# main.net
KiCad netlist of a schematic drawn in EAGLE
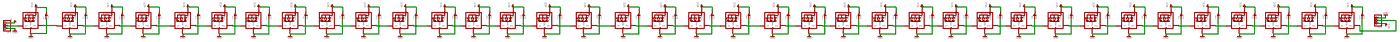
[diagram p0: schematic, sheet 1, overview]
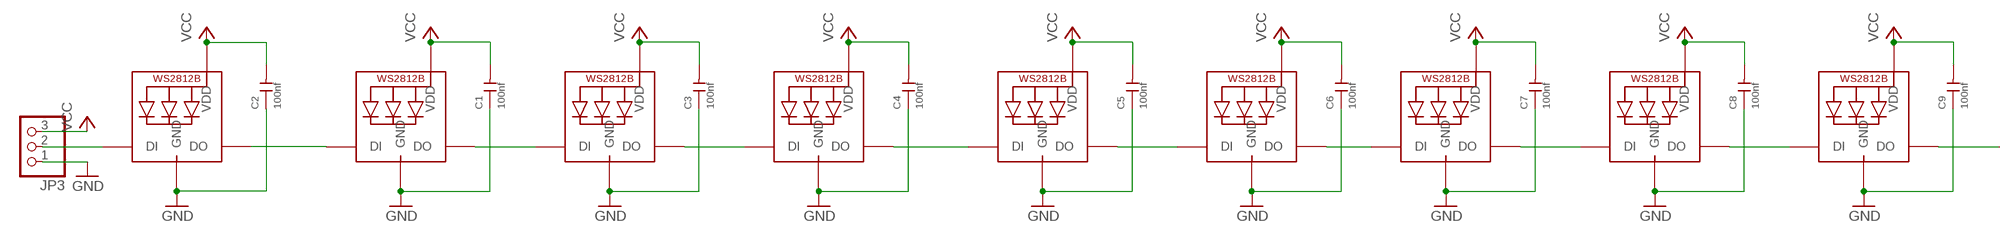
[diagram p1: schematic, sheet 1, part 1 of 4]
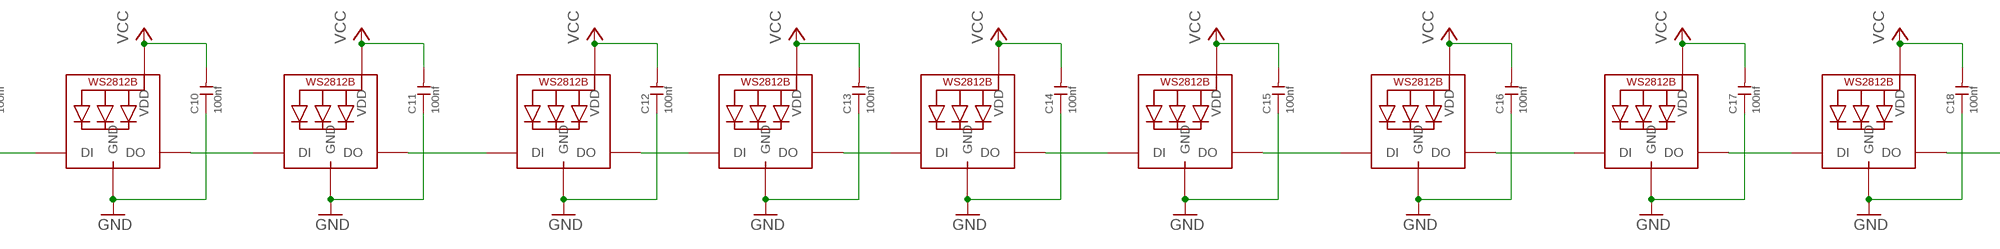
[diagram p2: schematic, sheet 1, part 2 of 4]
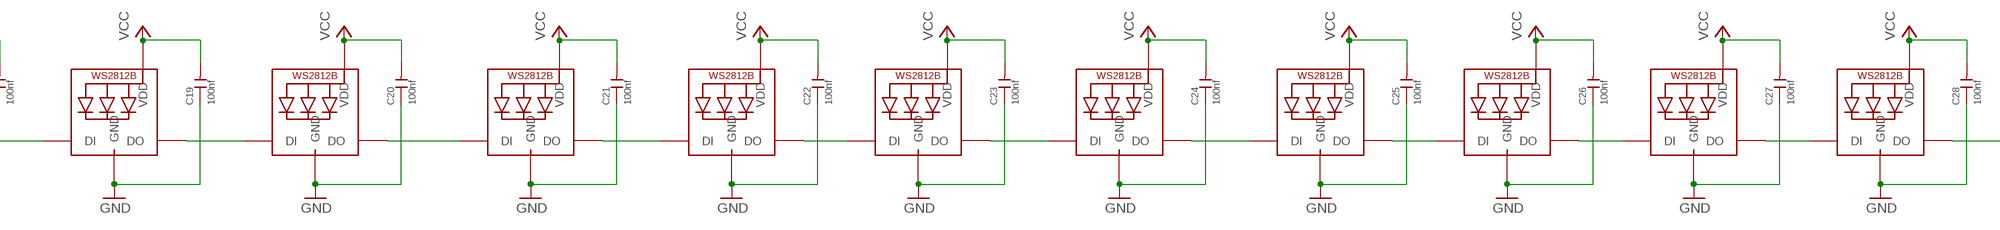
[diagram p3: schematic, sheet 1, part 3 of 4]
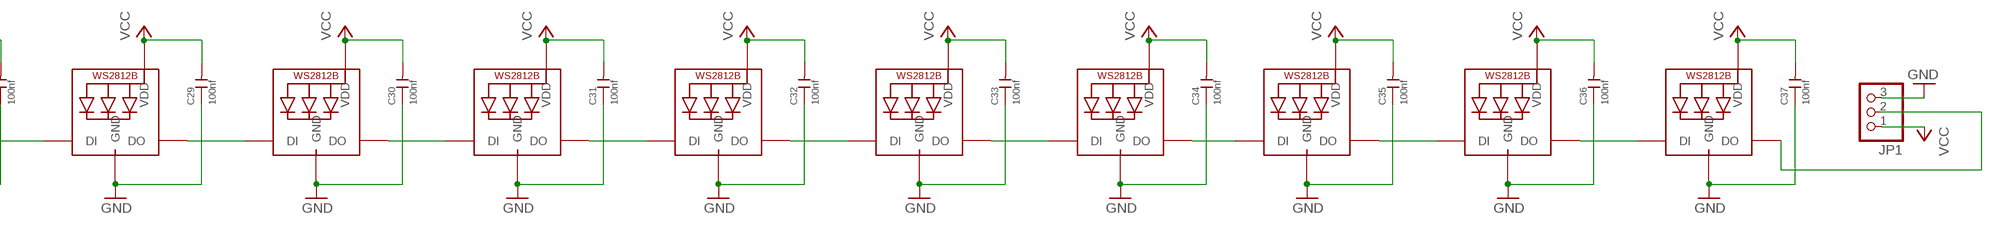
[diagram p4: schematic, sheet 1, part 4 of 4]

(export (version "E")
  (design (tool "Eeschema 10.0.6"))
  (components
    (comp (ref "C1")
      (value "100nf")
      (footprint "eagle-import:C0402")
      (fields (field (name "MPN") "CC0402KRX7R8BB104"))
      (libsource (lib "eagle-import") (part "CERAMIC-100NF-25V-10%-X7R(0402)"))
    )
    (comp (ref "C2")
      (value "100nf")
      (footprint "eagle-import:C0402")
      (fields (field (name "MPN") "CC0402KRX7R8BB104"))
      (libsource (lib "eagle-import") (part "CERAMIC-100NF-25V-10%-X7R(0402)"))
    )
    (comp (ref "C3")
      (value "100nf")
      (footprint "eagle-import:C0402")
      (fields (field (name "MPN") "CC0402KRX7R8BB104"))
      (libsource (lib "eagle-import") (part "CERAMIC-100NF-25V-10%-X7R(0402)"))
    )
    (comp (ref "C4")
      (value "100nf")
      (footprint "eagle-import:C0402")
      (fields (field (name "MPN") "CC0402KRX7R8BB104"))
      (libsource (lib "eagle-import") (part "CERAMIC-100NF-25V-10%-X7R(0402)"))
    )
    (comp (ref "C5")
      (value "100nf")
      (footprint "eagle-import:C0402")
      (fields (field (name "MPN") "CC0402KRX7R8BB104"))
      (libsource (lib "eagle-import") (part "CERAMIC-100NF-25V-10%-X7R(0402)"))
    )
    (comp (ref "C6")
      (value "100nf")
      (footprint "eagle-import:C0402")
      (fields (field (name "MPN") "CC0402KRX7R8BB104"))
      (libsource (lib "eagle-import") (part "CERAMIC-100NF-25V-10%-X7R(0402)"))
    )
    (comp (ref "C7")
      (value "100nf")
      (footprint "eagle-import:C0402")
      (fields (field (name "MPN") "CC0402KRX7R8BB104"))
      (libsource (lib "eagle-import") (part "CERAMIC-100NF-25V-10%-X7R(0402)"))
    )
    (comp (ref "C8")
      (value "100nf")
      (footprint "eagle-import:C0402")
      (fields (field (name "MPN") "CC0402KRX7R8BB104"))
      (libsource (lib "eagle-import") (part "CERAMIC-100NF-25V-10%-X7R(0402)"))
    )
    (comp (ref "C9")
      (value "100nf")
      (footprint "eagle-import:C0402")
      (fields (field (name "MPN") "CC0402KRX7R8BB104"))
      (libsource (lib "eagle-import") (part "CERAMIC-100NF-25V-10%-X7R(0402)"))
    )
    (comp (ref "C10")
      (value "100nf")
      (footprint "eagle-import:C0402")
      (fields (field (name "MPN") "CC0402KRX7R8BB104"))
      (libsource (lib "eagle-import") (part "CERAMIC-100NF-25V-10%-X7R(0402)"))
    )
    (comp (ref "C11")
      (value "100nf")
      (footprint "eagle-import:C0402")
      (fields (field (name "MPN") "CC0402KRX7R8BB104"))
      (libsource (lib "eagle-import") (part "CERAMIC-100NF-25V-10%-X7R(0402)"))
    )
    (comp (ref "C12")
      (value "100nf")
      (footprint "eagle-import:C0402")
      (fields (field (name "MPN") "CC0402KRX7R8BB104"))
      (libsource (lib "eagle-import") (part "CERAMIC-100NF-25V-10%-X7R(0402)"))
    )
    (comp (ref "C13")
      (value "100nf")
      (footprint "eagle-import:C0402")
      (fields (field (name "MPN") "CC0402KRX7R8BB104"))
      (libsource (lib "eagle-import") (part "CERAMIC-100NF-25V-10%-X7R(0402)"))
    )
    (comp (ref "C14")
      (value "100nf")
      (footprint "eagle-import:C0402")
      (fields (field (name "MPN") "CC0402KRX7R8BB104"))
      (libsource (lib "eagle-import") (part "CERAMIC-100NF-25V-10%-X7R(0402)"))
    )
    (comp (ref "C15")
      (value "100nf")
      (footprint "eagle-import:C0402")
      (fields (field (name "MPN") "CC0402KRX7R8BB104"))
      (libsource (lib "eagle-import") (part "CERAMIC-100NF-25V-10%-X7R(0402)"))
    )
    (comp (ref "C16")
      (value "100nf")
      (footprint "eagle-import:C0402")
      (fields (field (name "MPN") "CC0402KRX7R8BB104"))
      (libsource (lib "eagle-import") (part "CERAMIC-100NF-25V-10%-X7R(0402)"))
    )
    (comp (ref "C17")
      (value "100nf")
      (footprint "eagle-import:C0402")
      (fields (field (name "MPN") "CC0402KRX7R8BB104"))
      (libsource (lib "eagle-import") (part "CERAMIC-100NF-25V-10%-X7R(0402)"))
    )
    (comp (ref "C18")
      (value "100nf")
      (footprint "eagle-import:C0402")
      (fields (field (name "MPN") "CC0402KRX7R8BB104"))
      (libsource (lib "eagle-import") (part "CERAMIC-100NF-25V-10%-X7R(0402)"))
    )
    (comp (ref "C19")
      (value "100nf")
      (footprint "eagle-import:C0402")
      (fields (field (name "MPN") "CC0402KRX7R8BB104"))
      (libsource (lib "eagle-import") (part "CERAMIC-100NF-25V-10%-X7R(0402)"))
    )
    (comp (ref "C20")
      (value "100nf")
      (footprint "eagle-import:C0402")
      (fields (field (name "MPN") "CC0402KRX7R8BB104"))
      (libsource (lib "eagle-import") (part "CERAMIC-100NF-25V-10%-X7R(0402)"))
    )
    (comp (ref "C21")
      (value "100nf")
      (footprint "eagle-import:C0402")
      (fields (field (name "MPN") "CC0402KRX7R8BB104"))
      (libsource (lib "eagle-import") (part "CERAMIC-100NF-25V-10%-X7R(0402)"))
    )
    (comp (ref "C22")
      (value "100nf")
      (footprint "eagle-import:C0402")
      (fields (field (name "MPN") "CC0402KRX7R8BB104"))
      (libsource (lib "eagle-import") (part "CERAMIC-100NF-25V-10%-X7R(0402)"))
    )
    (comp (ref "C23")
      (value "100nf")
      (footprint "eagle-import:C0402")
      (fields (field (name "MPN") "CC0402KRX7R8BB104"))
      (libsource (lib "eagle-import") (part "CERAMIC-100NF-25V-10%-X7R(0402)"))
    )
    (comp (ref "C24")
      (value "100nf")
      (footprint "eagle-import:C0402")
      (fields (field (name "MPN") "CC0402KRX7R8BB104"))
      (libsource (lib "eagle-import") (part "CERAMIC-100NF-25V-10%-X7R(0402)"))
    )
    (comp (ref "C25")
      (value "100nf")
      (footprint "eagle-import:C0402")
      (fields (field (name "MPN") "CC0402KRX7R8BB104"))
      (libsource (lib "eagle-import") (part "CERAMIC-100NF-25V-10%-X7R(0402)"))
    )
    (comp (ref "C26")
      (value "100nf")
      (footprint "eagle-import:C0402")
      (fields (field (name "MPN") "CC0402KRX7R8BB104"))
      (libsource (lib "eagle-import") (part "CERAMIC-100NF-25V-10%-X7R(0402)"))
    )
    (comp (ref "C27")
      (value "100nf")
      (footprint "eagle-import:C0402")
      (fields (field (name "MPN") "CC0402KRX7R8BB104"))
      (libsource (lib "eagle-import") (part "CERAMIC-100NF-25V-10%-X7R(0402)"))
    )
    (comp (ref "C28")
      (value "100nf")
      (footprint "eagle-import:C0402")
      (fields (field (name "MPN") "CC0402KRX7R8BB104"))
      (libsource (lib "eagle-import") (part "CERAMIC-100NF-25V-10%-X7R(0402)"))
    )
    (comp (ref "C29")
      (value "100nf")
      (footprint "eagle-import:C0402")
      (fields (field (name "MPN") "CC0402KRX7R8BB104"))
      (libsource (lib "eagle-import") (part "CERAMIC-100NF-25V-10%-X7R(0402)"))
    )
    (comp (ref "C30")
      (value "100nf")
      (footprint "eagle-import:C0402")
      (fields (field (name "MPN") "CC0402KRX7R8BB104"))
      (libsource (lib "eagle-import") (part "CERAMIC-100NF-25V-10%-X7R(0402)"))
    )
    (comp (ref "C31")
      (value "100nf")
      (footprint "eagle-import:C0402")
      (fields (field (name "MPN") "CC0402KRX7R8BB104"))
      (libsource (lib "eagle-import") (part "CERAMIC-100NF-25V-10%-X7R(0402)"))
    )
    (comp (ref "C32")
      (value "100nf")
      (footprint "eagle-import:C0402")
      (fields (field (name "MPN") "CC0402KRX7R8BB104"))
      (libsource (lib "eagle-import") (part "CERAMIC-100NF-25V-10%-X7R(0402)"))
    )
    (comp (ref "C33")
      (value "100nf")
      (footprint "eagle-import:C0402")
      (fields (field (name "MPN") "CC0402KRX7R8BB104"))
      (libsource (lib "eagle-import") (part "CERAMIC-100NF-25V-10%-X7R(0402)"))
    )
    (comp (ref "C34")
      (value "100nf")
      (footprint "eagle-import:C0402")
      (fields (field (name "MPN") "CC0402KRX7R8BB104"))
      (libsource (lib "eagle-import") (part "CERAMIC-100NF-25V-10%-X7R(0402)"))
    )
    (comp (ref "C35")
      (value "100nf")
      (footprint "eagle-import:C0402")
      (fields (field (name "MPN") "CC0402KRX7R8BB104"))
      (libsource (lib "eagle-import") (part "CERAMIC-100NF-25V-10%-X7R(0402)"))
    )
    (comp (ref "C36")
      (value "100nf")
      (footprint "eagle-import:C0402")
      (fields (field (name "MPN") "CC0402KRX7R8BB104"))
      (libsource (lib "eagle-import") (part "CERAMIC-100NF-25V-10%-X7R(0402)"))
    )
    (comp (ref "C37")
      (value "100nf")
      (footprint "eagle-import:C0402")
      (fields (field (name "MPN") "CC0402KRX7R8BB104"))
      (libsource (lib "eagle-import") (part "CERAMIC-100NF-25V-10%-X7R(0402)"))
    )
    (comp (ref "JP1")
      (value "PINHD-1X3")
      (footprint "eagle-import:1X03")
      (libsource (lib "eagle-import") (part "PINHD-1X3"))
    )
    (comp (ref "JP3")
      (value "PINHD-1X3")
      (footprint "eagle-import:1X03")
      (libsource (lib "eagle-import") (part "PINHD-1X3"))
    )
    (comp (ref "L")
      (value "WS2812B5050")
      (footprint "eagle-import:WS2812B")
      (libsource (lib "eagle-import") (part "WS2812B5050"))
    )
    (comp (ref "LED1")
      (value "WS2812B5050")
      (footprint "eagle-import:WS2812B")
      (libsource (lib "eagle-import") (part "WS2812B5050"))
    )
    (comp (ref "LED3")
      (value "WS2812B5050")
      (footprint "eagle-import:WS2812B")
      (libsource (lib "eagle-import") (part "WS2812B5050"))
    )
    (comp (ref "LED4")
      (value "WS2812B5050")
      (footprint "eagle-import:WS2812B")
      (libsource (lib "eagle-import") (part "WS2812B5050"))
    )
    (comp (ref "LED5")
      (value "WS2812B5050")
      (footprint "eagle-import:WS2812B")
      (libsource (lib "eagle-import") (part "WS2812B5050"))
    )
    (comp (ref "LED6")
      (value "WS2812B5050")
      (footprint "eagle-import:WS2812B")
      (libsource (lib "eagle-import") (part "WS2812B5050"))
    )
    (comp (ref "LED7")
      (value "WS2812B5050")
      (footprint "eagle-import:WS2812B")
      (libsource (lib "eagle-import") (part "WS2812B5050"))
    )
    (comp (ref "LED8")
      (value "WS2812B5050")
      (footprint "eagle-import:WS2812B")
      (libsource (lib "eagle-import") (part "WS2812B5050"))
    )
    (comp (ref "LED9")
      (value "WS2812B5050")
      (footprint "eagle-import:WS2812B")
      (libsource (lib "eagle-import") (part "WS2812B5050"))
    )
    (comp (ref "LED10")
      (value "WS2812B5050")
      (footprint "eagle-import:WS2812B")
      (libsource (lib "eagle-import") (part "WS2812B5050"))
    )
    (comp (ref "LED11")
      (value "WS2812B5050")
      (footprint "eagle-import:WS2812B")
      (libsource (lib "eagle-import") (part "WS2812B5050"))
    )
    (comp (ref "LED12")
      (value "WS2812B5050")
      (footprint "eagle-import:WS2812B")
      (libsource (lib "eagle-import") (part "WS2812B5050"))
    )
    (comp (ref "LED13")
      (value "WS2812B5050")
      (footprint "eagle-import:WS2812B")
      (libsource (lib "eagle-import") (part "WS2812B5050"))
    )
    (comp (ref "LED14")
      (value "WS2812B5050")
      (footprint "eagle-import:WS2812B")
      (libsource (lib "eagle-import") (part "WS2812B5050"))
    )
    (comp (ref "LED15")
      (value "WS2812B5050")
      (footprint "eagle-import:WS2812B")
      (libsource (lib "eagle-import") (part "WS2812B5050"))
    )
    (comp (ref "LED16")
      (value "WS2812B5050")
      (footprint "eagle-import:WS2812B")
      (libsource (lib "eagle-import") (part "WS2812B5050"))
    )
    (comp (ref "LED17")
      (value "WS2812B5050")
      (footprint "eagle-import:WS2812B")
      (libsource (lib "eagle-import") (part "WS2812B5050"))
    )
    (comp (ref "LED18")
      (value "WS2812B5050")
      (footprint "eagle-import:WS2812B")
      (libsource (lib "eagle-import") (part "WS2812B5050"))
    )
    (comp (ref "LED19")
      (value "WS2812B5050")
      (footprint "eagle-import:WS2812B")
      (libsource (lib "eagle-import") (part "WS2812B5050"))
    )
    (comp (ref "LED20")
      (value "WS2812B5050")
      (footprint "eagle-import:WS2812B")
      (libsource (lib "eagle-import") (part "WS2812B5050"))
    )
    (comp (ref "LED21")
      (value "WS2812B5050")
      (footprint "eagle-import:WS2812B")
      (libsource (lib "eagle-import") (part "WS2812B5050"))
    )
    (comp (ref "LED22")
      (value "WS2812B5050")
      (footprint "eagle-import:WS2812B")
      (libsource (lib "eagle-import") (part "WS2812B5050"))
    )
    (comp (ref "LED23")
      (value "WS2812B5050")
      (footprint "eagle-import:WS2812B")
      (libsource (lib "eagle-import") (part "WS2812B5050"))
    )
    (comp (ref "LED24")
      (value "WS2812B5050")
      (footprint "eagle-import:WS2812B")
      (libsource (lib "eagle-import") (part "WS2812B5050"))
    )
    (comp (ref "LED25")
      (value "WS2812B5050")
      (footprint "eagle-import:WS2812B")
      (libsource (lib "eagle-import") (part "WS2812B5050"))
    )
    (comp (ref "LED26")
      (value "WS2812B5050")
      (footprint "eagle-import:WS2812B")
      (libsource (lib "eagle-import") (part "WS2812B5050"))
    )
    (comp (ref "LED27")
      (value "WS2812B5050")
      (footprint "eagle-import:WS2812B")
      (libsource (lib "eagle-import") (part "WS2812B5050"))
    )
    (comp (ref "LED28")
      (value "WS2812B5050")
      (footprint "eagle-import:WS2812B")
      (libsource (lib "eagle-import") (part "WS2812B5050"))
    )
    (comp (ref "LED29")
      (value "WS2812B5050")
      (footprint "eagle-import:WS2812B")
      (libsource (lib "eagle-import") (part "WS2812B5050"))
    )
    (comp (ref "LED30")
      (value "WS2812B5050")
      (footprint "eagle-import:WS2812B")
      (libsource (lib "eagle-import") (part "WS2812B5050"))
    )
    (comp (ref "LED31")
      (value "WS2812B5050")
      (footprint "eagle-import:WS2812B")
      (libsource (lib "eagle-import") (part "WS2812B5050"))
    )
    (comp (ref "LED32")
      (value "WS2812B5050")
      (footprint "eagle-import:WS2812B")
      (libsource (lib "eagle-import") (part "WS2812B5050"))
    )
    (comp (ref "LED33")
      (value "WS2812B5050")
      (footprint "eagle-import:WS2812B")
      (libsource (lib "eagle-import") (part "WS2812B5050"))
    )
    (comp (ref "LED34")
      (value "WS2812B5050")
      (footprint "eagle-import:WS2812B")
      (libsource (lib "eagle-import") (part "WS2812B5050"))
    )
    (comp (ref "LED35")
      (value "WS2812B5050")
      (footprint "eagle-import:WS2812B")
      (libsource (lib "eagle-import") (part "WS2812B5050"))
    )
    (comp (ref "LED36")
      (value "WS2812B5050")
      (footprint "eagle-import:WS2812B")
      (libsource (lib "eagle-import") (part "WS2812B5050"))
    )
    (comp (ref "LED37")
      (value "WS2812B5050")
      (footprint "eagle-import:WS2812B")
      (libsource (lib "eagle-import") (part "WS2812B5050"))
    )
  )
  (nets
    (net (code "1") (name "GND") (class "Default")
      (node (ref "C1") (pin "1") (pinfunction "1_1") (pintype "passive"))
      (node (ref "C10") (pin "1") (pinfunction "1_1") (pintype "passive"))
      (node (ref "C11") (pin "1") (pinfunction "1_1") (pintype "passive"))
      (node (ref "C12") (pin "1") (pinfunction "1_1") (pintype "passive"))
      (node (ref "C13") (pin "1") (pinfunction "1_1") (pintype "passive"))
      (node (ref "C14") (pin "1") (pinfunction "1_1") (pintype "passive"))
      (node (ref "C15") (pin "1") (pinfunction "1_1") (pintype "passive"))
      (node (ref "C16") (pin "1") (pinfunction "1_1") (pintype "passive"))
      (node (ref "C17") (pin "1") (pinfunction "1_1") (pintype "passive"))
      (node (ref "C18") (pin "1") (pinfunction "1_1") (pintype "passive"))
      (node (ref "C19") (pin "1") (pinfunction "1_1") (pintype "passive"))
      (node (ref "C2") (pin "1") (pinfunction "1_1") (pintype "passive"))
      (node (ref "C20") (pin "1") (pinfunction "1_1") (pintype "passive"))
      (node (ref "C21") (pin "1") (pinfunction "1_1") (pintype "passive"))
      (node (ref "C22") (pin "1") (pinfunction "1_1") (pintype "passive"))
      (node (ref "C23") (pin "1") (pinfunction "1_1") (pintype "passive"))
      (node (ref "C24") (pin "1") (pinfunction "1_1") (pintype "passive"))
      (node (ref "C25") (pin "1") (pinfunction "1_1") (pintype "passive"))
      (node (ref "C26") (pin "1") (pinfunction "1_1") (pintype "passive"))
      (node (ref "C27") (pin "1") (pinfunction "1_1") (pintype "passive"))
      (node (ref "C28") (pin "1") (pinfunction "1_1") (pintype "passive"))
      (node (ref "C29") (pin "1") (pinfunction "1_1") (pintype "passive"))
      (node (ref "C3") (pin "1") (pinfunction "1_1") (pintype "passive"))
      (node (ref "C30") (pin "1") (pinfunction "1_1") (pintype "passive"))
      (node (ref "C31") (pin "1") (pinfunction "1_1") (pintype "passive"))
      (node (ref "C32") (pin "1") (pinfunction "1_1") (pintype "passive"))
      (node (ref "C33") (pin "1") (pinfunction "1_1") (pintype "passive"))
      (node (ref "C34") (pin "1") (pinfunction "1_1") (pintype "passive"))
      (node (ref "C35") (pin "1") (pinfunction "1_1") (pintype "passive"))
      (node (ref "C36") (pin "1") (pinfunction "1_1") (pintype "passive"))
      (node (ref "C37") (pin "1") (pinfunction "1_1") (pintype "passive"))
      (node (ref "C4") (pin "1") (pinfunction "1_1") (pintype "passive"))
      (node (ref "C5") (pin "1") (pinfunction "1_1") (pintype "passive"))
      (node (ref "C6") (pin "1") (pinfunction "1_1") (pintype "passive"))
      (node (ref "C7") (pin "1") (pinfunction "1_1") (pintype "passive"))
      (node (ref "C8") (pin "1") (pinfunction "1_1") (pintype "passive"))
      (node (ref "C9") (pin "1") (pinfunction "1_1") (pintype "passive"))
      (node (ref "JP1") (pin "3") (pinfunction "3_3") (pintype "passive"))
      (node (ref "JP3") (pin "1") (pinfunction "1_1") (pintype "passive"))
      (node (ref "L") (pin "3-GND") (pinfunction "GND_3-GND") (pintype "power_in"))
      (node (ref "LED1") (pin "3-GND") (pinfunction "GND_3-GND") (pintype "power_in"))
      (node (ref "LED10") (pin "3-GND") (pinfunction "GND_3-GND") (pintype "power_in"))
      (node (ref "LED11") (pin "3-GND") (pinfunction "GND_3-GND") (pintype "power_in"))
      (node (ref "LED12") (pin "3-GND") (pinfunction "GND_3-GND") (pintype "power_in"))
      (node (ref "LED13") (pin "3-GND") (pinfunction "GND_3-GND") (pintype "power_in"))
      (node (ref "LED14") (pin "3-GND") (pinfunction "GND_3-GND") (pintype "power_in"))
      (node (ref "LED15") (pin "3-GND") (pinfunction "GND_3-GND") (pintype "power_in"))
      (node (ref "LED16") (pin "3-GND") (pinfunction "GND_3-GND") (pintype "power_in"))
      (node (ref "LED17") (pin "3-GND") (pinfunction "GND_3-GND") (pintype "power_in"))
      (node (ref "LED18") (pin "3-GND") (pinfunction "GND_3-GND") (pintype "power_in"))
      (node (ref "LED19") (pin "3-GND") (pinfunction "GND_3-GND") (pintype "power_in"))
      (node (ref "LED20") (pin "3-GND") (pinfunction "GND_3-GND") (pintype "power_in"))
      (node (ref "LED21") (pin "3-GND") (pinfunction "GND_3-GND") (pintype "power_in"))
      (node (ref "LED22") (pin "3-GND") (pinfunction "GND_3-GND") (pintype "power_in"))
      (node (ref "LED23") (pin "3-GND") (pinfunction "GND_3-GND") (pintype "power_in"))
      (node (ref "LED24") (pin "3-GND") (pinfunction "GND_3-GND") (pintype "power_in"))
      (node (ref "LED25") (pin "3-GND") (pinfunction "GND_3-GND") (pintype "power_in"))
      (node (ref "LED26") (pin "3-GND") (pinfunction "GND_3-GND") (pintype "power_in"))
      (node (ref "LED27") (pin "3-GND") (pinfunction "GND_3-GND") (pintype "power_in"))
      (node (ref "LED28") (pin "3-GND") (pinfunction "GND_3-GND") (pintype "power_in"))
      (node (ref "LED29") (pin "3-GND") (pinfunction "GND_3-GND") (pintype "power_in"))
      (node (ref "LED3") (pin "3-GND") (pinfunction "GND_3-GND") (pintype "power_in"))
      (node (ref "LED30") (pin "3-GND") (pinfunction "GND_3-GND") (pintype "power_in"))
      (node (ref "LED31") (pin "3-GND") (pinfunction "GND_3-GND") (pintype "power_in"))
      (node (ref "LED32") (pin "3-GND") (pinfunction "GND_3-GND") (pintype "power_in"))
      (node (ref "LED33") (pin "3-GND") (pinfunction "GND_3-GND") (pintype "power_in"))
      (node (ref "LED34") (pin "3-GND") (pinfunction "GND_3-GND") (pintype "power_in"))
      (node (ref "LED35") (pin "3-GND") (pinfunction "GND_3-GND") (pintype "power_in"))
      (node (ref "LED36") (pin "3-GND") (pinfunction "GND_3-GND") (pintype "power_in"))
      (node (ref "LED37") (pin "3-GND") (pinfunction "GND_3-GND") (pintype "power_in"))
      (node (ref "LED4") (pin "3-GND") (pinfunction "GND_3-GND") (pintype "power_in"))
      (node (ref "LED5") (pin "3-GND") (pinfunction "GND_3-GND") (pintype "power_in"))
      (node (ref "LED6") (pin "3-GND") (pinfunction "GND_3-GND") (pintype "power_in"))
      (node (ref "LED7") (pin "3-GND") (pinfunction "GND_3-GND") (pintype "power_in"))
      (node (ref "LED8") (pin "3-GND") (pinfunction "GND_3-GND") (pintype "power_in"))
      (node (ref "LED9") (pin "3-GND") (pinfunction "GND_3-GND") (pintype "power_in"))
    )
    (net (code "2") (name "Net-(L-DI)") (class "Default")
      (node (ref "JP3") (pin "2") (pinfunction "2_2") (pintype "passive"))
      (node (ref "L") (pin "4-DIN") (pinfunction "DI_4-DIN") (pintype "input"))
    )
    (net (code "3") (name "Net-(L-DO)") (class "Default")
      (node (ref "L") (pin "2-DOUT") (pinfunction "DO_2-DOUT") (pintype "output"))
      (node (ref "LED1") (pin "4-DIN") (pinfunction "DI_4-DIN") (pintype "input"))
    )
    (net (code "4") (name "Net-(LED1-DO)") (class "Default")
      (node (ref "LED1") (pin "2-DOUT") (pinfunction "DO_2-DOUT") (pintype "output"))
      (node (ref "LED3") (pin "4-DIN") (pinfunction "DI_4-DIN") (pintype "input"))
    )
    (net (code "5") (name "Net-(LED3-DO)") (class "Default")
      (node (ref "LED3") (pin "2-DOUT") (pinfunction "DO_2-DOUT") (pintype "output"))
      (node (ref "LED4") (pin "4-DIN") (pinfunction "DI_4-DIN") (pintype "input"))
    )
    (net (code "6") (name "Net-(LED4-DO)") (class "Default")
      (node (ref "LED4") (pin "2-DOUT") (pinfunction "DO_2-DOUT") (pintype "output"))
      (node (ref "LED5") (pin "4-DIN") (pinfunction "DI_4-DIN") (pintype "input"))
    )
    (net (code "7") (name "Net-(LED5-DO)") (class "Default")
      (node (ref "LED5") (pin "2-DOUT") (pinfunction "DO_2-DOUT") (pintype "output"))
      (node (ref "LED6") (pin "4-DIN") (pinfunction "DI_4-DIN") (pintype "input"))
    )
    (net (code "8") (name "Net-(LED6-DO)") (class "Default")
      (node (ref "LED6") (pin "2-DOUT") (pinfunction "DO_2-DOUT") (pintype "output"))
      (node (ref "LED7") (pin "4-DIN") (pinfunction "DI_4-DIN") (pintype "input"))
    )
    (net (code "9") (name "Net-(LED7-DO)") (class "Default")
      (node (ref "LED7") (pin "2-DOUT") (pinfunction "DO_2-DOUT") (pintype "output"))
      (node (ref "LED8") (pin "4-DIN") (pinfunction "DI_4-DIN") (pintype "input"))
    )
    (net (code "10") (name "Net-(LED8-DO)") (class "Default")
      (node (ref "LED8") (pin "2-DOUT") (pinfunction "DO_2-DOUT") (pintype "output"))
      (node (ref "LED9") (pin "4-DIN") (pinfunction "DI_4-DIN") (pintype "input"))
    )
    (net (code "11") (name "Net-(LED10-DI)") (class "Default")
      (node (ref "LED10") (pin "4-DIN") (pinfunction "DI_4-DIN") (pintype "input"))
      (node (ref "LED9") (pin "2-DOUT") (pinfunction "DO_2-DOUT") (pintype "output"))
    )
    (net (code "12") (name "Net-(LED10-DO)") (class "Default")
      (node (ref "LED10") (pin "2-DOUT") (pinfunction "DO_2-DOUT") (pintype "output"))
      (node (ref "LED11") (pin "4-DIN") (pinfunction "DI_4-DIN") (pintype "input"))
    )
    (net (code "13") (name "Net-(LED11-DO)") (class "Default")
      (node (ref "LED11") (pin "2-DOUT") (pinfunction "DO_2-DOUT") (pintype "output"))
      (node (ref "LED12") (pin "4-DIN") (pinfunction "DI_4-DIN") (pintype "input"))
    )
    (net (code "14") (name "Net-(LED12-DO)") (class "Default")
      (node (ref "LED12") (pin "2-DOUT") (pinfunction "DO_2-DOUT") (pintype "output"))
      (node (ref "LED13") (pin "4-DIN") (pinfunction "DI_4-DIN") (pintype "input"))
    )
    (net (code "15") (name "Net-(LED13-DO)") (class "Default")
      (node (ref "LED13") (pin "2-DOUT") (pinfunction "DO_2-DOUT") (pintype "output"))
      (node (ref "LED14") (pin "4-DIN") (pinfunction "DI_4-DIN") (pintype "input"))
    )
    (net (code "16") (name "Net-(LED14-DO)") (class "Default")
      (node (ref "LED14") (pin "2-DOUT") (pinfunction "DO_2-DOUT") (pintype "output"))
      (node (ref "LED15") (pin "4-DIN") (pinfunction "DI_4-DIN") (pintype "input"))
    )
    (net (code "17") (name "Net-(LED15-DO)") (class "Default")
      (node (ref "LED15") (pin "2-DOUT") (pinfunction "DO_2-DOUT") (pintype "output"))
      (node (ref "LED16") (pin "4-DIN") (pinfunction "DI_4-DIN") (pintype "input"))
    )
    (net (code "18") (name "Net-(LED16-DO)") (class "Default")
      (node (ref "LED16") (pin "2-DOUT") (pinfunction "DO_2-DOUT") (pintype "output"))
      (node (ref "LED17") (pin "4-DIN") (pinfunction "DI_4-DIN") (pintype "input"))
    )
    (net (code "19") (name "Net-(LED17-DO)") (class "Default")
      (node (ref "LED17") (pin "2-DOUT") (pinfunction "DO_2-DOUT") (pintype "output"))
      (node (ref "LED18") (pin "4-DIN") (pinfunction "DI_4-DIN") (pintype "input"))
    )
    (net (code "20") (name "Net-(LED18-DO)") (class "Default")
      (node (ref "LED18") (pin "2-DOUT") (pinfunction "DO_2-DOUT") (pintype "output"))
      (node (ref "LED19") (pin "4-DIN") (pinfunction "DI_4-DIN") (pintype "input"))
    )
    (net (code "21") (name "Net-(LED19-DO)") (class "Default")
      (node (ref "LED19") (pin "2-DOUT") (pinfunction "DO_2-DOUT") (pintype "output"))
      (node (ref "LED20") (pin "4-DIN") (pinfunction "DI_4-DIN") (pintype "input"))
    )
    (net (code "22") (name "Net-(LED20-DO)") (class "Default")
      (node (ref "LED20") (pin "2-DOUT") (pinfunction "DO_2-DOUT") (pintype "output"))
      (node (ref "LED21") (pin "4-DIN") (pinfunction "DI_4-DIN") (pintype "input"))
    )
    (net (code "23") (name "Net-(LED21-DO)") (class "Default")
      (node (ref "LED21") (pin "2-DOUT") (pinfunction "DO_2-DOUT") (pintype "output"))
      (node (ref "LED22") (pin "4-DIN") (pinfunction "DI_4-DIN") (pintype "input"))
    )
    (net (code "24") (name "Net-(LED22-DO)") (class "Default")
      (node (ref "LED22") (pin "2-DOUT") (pinfunction "DO_2-DOUT") (pintype "output"))
      (node (ref "LED23") (pin "4-DIN") (pinfunction "DI_4-DIN") (pintype "input"))
    )
    (net (code "25") (name "Net-(LED23-DO)") (class "Default")
      (node (ref "LED23") (pin "2-DOUT") (pinfunction "DO_2-DOUT") (pintype "output"))
      (node (ref "LED24") (pin "4-DIN") (pinfunction "DI_4-DIN") (pintype "input"))
    )
    (net (code "26") (name "Net-(LED24-DO)") (class "Default")
      (node (ref "LED24") (pin "2-DOUT") (pinfunction "DO_2-DOUT") (pintype "output"))
      (node (ref "LED25") (pin "4-DIN") (pinfunction "DI_4-DIN") (pintype "input"))
    )
    (net (code "27") (name "Net-(LED25-DO)") (class "Default")
      (node (ref "LED25") (pin "2-DOUT") (pinfunction "DO_2-DOUT") (pintype "output"))
      (node (ref "LED26") (pin "4-DIN") (pinfunction "DI_4-DIN") (pintype "input"))
    )
    (net (code "28") (name "Net-(LED26-DO)") (class "Default")
      (node (ref "LED26") (pin "2-DOUT") (pinfunction "DO_2-DOUT") (pintype "output"))
      (node (ref "LED27") (pin "4-DIN") (pinfunction "DI_4-DIN") (pintype "input"))
    )
    (net (code "29") (name "Net-(LED27-DO)") (class "Default")
      (node (ref "LED27") (pin "2-DOUT") (pinfunction "DO_2-DOUT") (pintype "output"))
      (node (ref "LED28") (pin "4-DIN") (pinfunction "DI_4-DIN") (pintype "input"))
    )
    (net (code "30") (name "Net-(LED28-DO)") (class "Default")
      (node (ref "LED28") (pin "2-DOUT") (pinfunction "DO_2-DOUT") (pintype "output"))
      (node (ref "LED29") (pin "4-DIN") (pinfunction "DI_4-DIN") (pintype "input"))
    )
    (net (code "31") (name "Net-(LED29-DO)") (class "Default")
      (node (ref "LED29") (pin "2-DOUT") (pinfunction "DO_2-DOUT") (pintype "output"))
      (node (ref "LED30") (pin "4-DIN") (pinfunction "DI_4-DIN") (pintype "input"))
    )
    (net (code "32") (name "Net-(LED30-DO)") (class "Default")
      (node (ref "LED30") (pin "2-DOUT") (pinfunction "DO_2-DOUT") (pintype "output"))
      (node (ref "LED31") (pin "4-DIN") (pinfunction "DI_4-DIN") (pintype "input"))
    )
    (net (code "33") (name "Net-(LED31-DO)") (class "Default")
      (node (ref "LED31") (pin "2-DOUT") (pinfunction "DO_2-DOUT") (pintype "output"))
      (node (ref "LED32") (pin "4-DIN") (pinfunction "DI_4-DIN") (pintype "input"))
    )
    (net (code "34") (name "Net-(LED32-DO)") (class "Default")
      (node (ref "LED32") (pin "2-DOUT") (pinfunction "DO_2-DOUT") (pintype "output"))
      (node (ref "LED33") (pin "4-DIN") (pinfunction "DI_4-DIN") (pintype "input"))
    )
    (net (code "35") (name "Net-(LED33-DO)") (class "Default")
      (node (ref "LED33") (pin "2-DOUT") (pinfunction "DO_2-DOUT") (pintype "output"))
      (node (ref "LED34") (pin "4-DIN") (pinfunction "DI_4-DIN") (pintype "input"))
    )
    (net (code "36") (name "Net-(LED34-DO)") (class "Default")
      (node (ref "LED34") (pin "2-DOUT") (pinfunction "DO_2-DOUT") (pintype "output"))
      (node (ref "LED35") (pin "4-DIN") (pinfunction "DI_4-DIN") (pintype "input"))
    )
    (net (code "37") (name "Net-(LED35-DO)") (class "Default")
      (node (ref "LED35") (pin "2-DOUT") (pinfunction "DO_2-DOUT") (pintype "output"))
      (node (ref "LED36") (pin "4-DIN") (pinfunction "DI_4-DIN") (pintype "input"))
    )
    (net (code "38") (name "Net-(LED36-DO)") (class "Default")
      (node (ref "LED36") (pin "2-DOUT") (pinfunction "DO_2-DOUT") (pintype "output"))
      (node (ref "LED37") (pin "4-DIN") (pinfunction "DI_4-DIN") (pintype "input"))
    )
    (net (code "39") (name "Net-(LED37-DO)") (class "Default")
      (node (ref "JP1") (pin "2") (pinfunction "2_2") (pintype "passive"))
      (node (ref "LED37") (pin "2-DOUT") (pinfunction "DO_2-DOUT") (pintype "output"))
    )
    (net (code "40") (name "VCC") (class "Default")
      (node (ref "C1") (pin "2") (pinfunction "2_2") (pintype "passive"))
      (node (ref "C10") (pin "2") (pinfunction "2_2") (pintype "passive"))
      (node (ref "C11") (pin "2") (pinfunction "2_2") (pintype "passive"))
      (node (ref "C12") (pin "2") (pinfunction "2_2") (pintype "passive"))
      (node (ref "C13") (pin "2") (pinfunction "2_2") (pintype "passive"))
      (node (ref "C14") (pin "2") (pinfunction "2_2") (pintype "passive"))
      (node (ref "C15") (pin "2") (pinfunction "2_2") (pintype "passive"))
      (node (ref "C16") (pin "2") (pinfunction "2_2") (pintype "passive"))
      (node (ref "C17") (pin "2") (pinfunction "2_2") (pintype "passive"))
      (node (ref "C18") (pin "2") (pinfunction "2_2") (pintype "passive"))
      (node (ref "C19") (pin "2") (pinfunction "2_2") (pintype "passive"))
      (node (ref "C2") (pin "2") (pinfunction "2_2") (pintype "passive"))
      (node (ref "C20") (pin "2") (pinfunction "2_2") (pintype "passive"))
      (node (ref "C21") (pin "2") (pinfunction "2_2") (pintype "passive"))
      (node (ref "C22") (pin "2") (pinfunction "2_2") (pintype "passive"))
      (node (ref "C23") (pin "2") (pinfunction "2_2") (pintype "passive"))
      (node (ref "C24") (pin "2") (pinfunction "2_2") (pintype "passive"))
      (node (ref "C25") (pin "2") (pinfunction "2_2") (pintype "passive"))
      (node (ref "C26") (pin "2") (pinfunction "2_2") (pintype "passive"))
      (node (ref "C27") (pin "2") (pinfunction "2_2") (pintype "passive"))
      (node (ref "C28") (pin "2") (pinfunction "2_2") (pintype "passive"))
      (node (ref "C29") (pin "2") (pinfunction "2_2") (pintype "passive"))
      (node (ref "C3") (pin "2") (pinfunction "2_2") (pintype "passive"))
      (node (ref "C30") (pin "2") (pinfunction "2_2") (pintype "passive"))
      (node (ref "C31") (pin "2") (pinfunction "2_2") (pintype "passive"))
      (node (ref "C32") (pin "2") (pinfunction "2_2") (pintype "passive"))
      (node (ref "C33") (pin "2") (pinfunction "2_2") (pintype "passive"))
      (node (ref "C34") (pin "2") (pinfunction "2_2") (pintype "passive"))
      (node (ref "C35") (pin "2") (pinfunction "2_2") (pintype "passive"))
      (node (ref "C36") (pin "2") (pinfunction "2_2") (pintype "passive"))
      (node (ref "C37") (pin "2") (pinfunction "2_2") (pintype "passive"))
      (node (ref "C4") (pin "2") (pinfunction "2_2") (pintype "passive"))
      (node (ref "C5") (pin "2") (pinfunction "2_2") (pintype "passive"))
      (node (ref "C6") (pin "2") (pinfunction "2_2") (pintype "passive"))
      (node (ref "C7") (pin "2") (pinfunction "2_2") (pintype "passive"))
      (node (ref "C8") (pin "2") (pinfunction "2_2") (pintype "passive"))
      (node (ref "C9") (pin "2") (pinfunction "2_2") (pintype "passive"))
      (node (ref "JP1") (pin "1") (pinfunction "1_1") (pintype "passive"))
      (node (ref "JP3") (pin "3") (pinfunction "3_3") (pintype "passive"))
      (node (ref "L") (pin "1-VDD") (pinfunction "VDD_1-VDD") (pintype "power_in"))
      (node (ref "LED1") (pin "1-VDD") (pinfunction "VDD_1-VDD") (pintype "power_in"))
      (node (ref "LED10") (pin "1-VDD") (pinfunction "VDD_1-VDD") (pintype "power_in"))
      (node (ref "LED11") (pin "1-VDD") (pinfunction "VDD_1-VDD") (pintype "power_in"))
      (node (ref "LED12") (pin "1-VDD") (pinfunction "VDD_1-VDD") (pintype "power_in"))
      (node (ref "LED13") (pin "1-VDD") (pinfunction "VDD_1-VDD") (pintype "power_in"))
      (node (ref "LED14") (pin "1-VDD") (pinfunction "VDD_1-VDD") (pintype "power_in"))
      (node (ref "LED15") (pin "1-VDD") (pinfunction "VDD_1-VDD") (pintype "power_in"))
      (node (ref "LED16") (pin "1-VDD") (pinfunction "VDD_1-VDD") (pintype "power_in"))
      (node (ref "LED17") (pin "1-VDD") (pinfunction "VDD_1-VDD") (pintype "power_in"))
      (node (ref "LED18") (pin "1-VDD") (pinfunction "VDD_1-VDD") (pintype "power_in"))
      (node (ref "LED19") (pin "1-VDD") (pinfunction "VDD_1-VDD") (pintype "power_in"))
      (node (ref "LED20") (pin "1-VDD") (pinfunction "VDD_1-VDD") (pintype "power_in"))
      (node (ref "LED21") (pin "1-VDD") (pinfunction "VDD_1-VDD") (pintype "power_in"))
      (node (ref "LED22") (pin "1-VDD") (pinfunction "VDD_1-VDD") (pintype "power_in"))
      (node (ref "LED23") (pin "1-VDD") (pinfunction "VDD_1-VDD") (pintype "power_in"))
      (node (ref "LED24") (pin "1-VDD") (pinfunction "VDD_1-VDD") (pintype "power_in"))
      (node (ref "LED25") (pin "1-VDD") (pinfunction "VDD_1-VDD") (pintype "power_in"))
      (node (ref "LED26") (pin "1-VDD") (pinfunction "VDD_1-VDD") (pintype "power_in"))
      (node (ref "LED27") (pin "1-VDD") (pinfunction "VDD_1-VDD") (pintype "power_in"))
      (node (ref "LED28") (pin "1-VDD") (pinfunction "VDD_1-VDD") (pintype "power_in"))
      (node (ref "LED29") (pin "1-VDD") (pinfunction "VDD_1-VDD") (pintype "power_in"))
      (node (ref "LED3") (pin "1-VDD") (pinfunction "VDD_1-VDD") (pintype "power_in"))
      (node (ref "LED30") (pin "1-VDD") (pinfunction "VDD_1-VDD") (pintype "power_in"))
      (node (ref "LED31") (pin "1-VDD") (pinfunction "VDD_1-VDD") (pintype "power_in"))
      (node (ref "LED32") (pin "1-VDD") (pinfunction "VDD_1-VDD") (pintype "power_in"))
      (node (ref "LED33") (pin "1-VDD") (pinfunction "VDD_1-VDD") (pintype "power_in"))
      (node (ref "LED34") (pin "1-VDD") (pinfunction "VDD_1-VDD") (pintype "power_in"))
      (node (ref "LED35") (pin "1-VDD") (pinfunction "VDD_1-VDD") (pintype "power_in"))
      (node (ref "LED36") (pin "1-VDD") (pinfunction "VDD_1-VDD") (pintype "power_in"))
      (node (ref "LED37") (pin "1-VDD") (pinfunction "VDD_1-VDD") (pintype "power_in"))
      (node (ref "LED4") (pin "1-VDD") (pinfunction "VDD_1-VDD") (pintype "power_in"))
      (node (ref "LED5") (pin "1-VDD") (pinfunction "VDD_1-VDD") (pintype "power_in"))
      (node (ref "LED6") (pin "1-VDD") (pinfunction "VDD_1-VDD") (pintype "power_in"))
      (node (ref "LED7") (pin "1-VDD") (pinfunction "VDD_1-VDD") (pintype "power_in"))
      (node (ref "LED8") (pin "1-VDD") (pinfunction "VDD_1-VDD") (pintype "power_in"))
      (node (ref "LED9") (pin "1-VDD") (pinfunction "VDD_1-VDD") (pintype "power_in"))
    )
  )
)
